# ST25R.net
KiCad netlist of a schematic drawn in Altium Designer
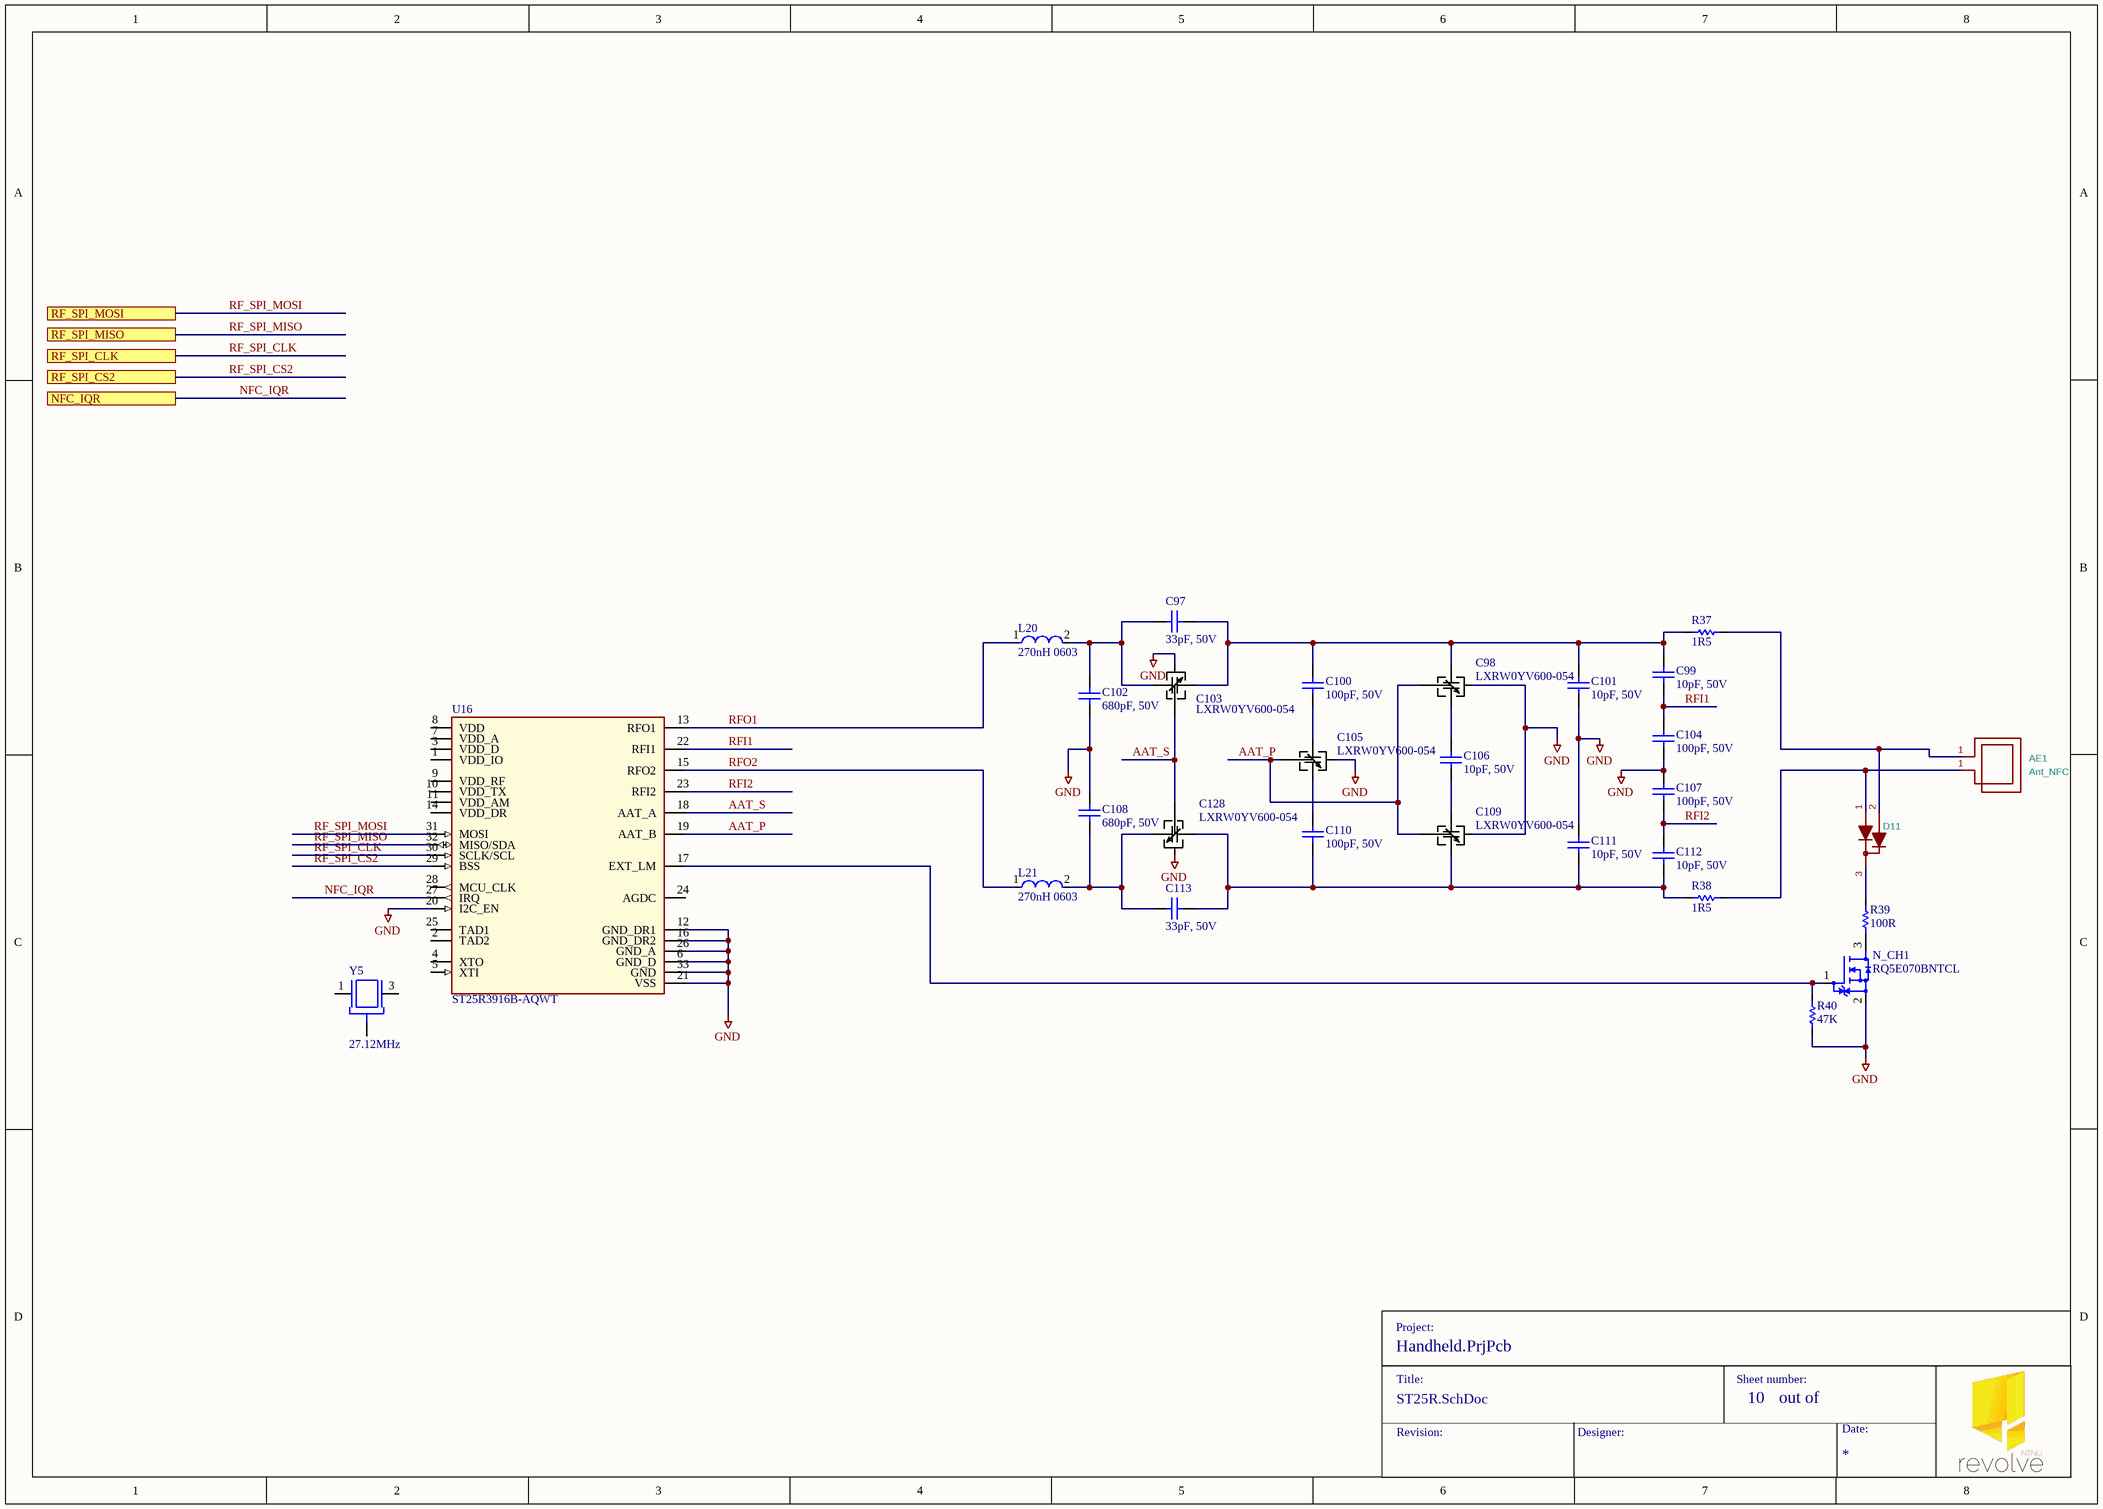
[diagram p0: ST25R.SchDoc]

(export (version "E")
  (design (tool "Eeschema 10.0.6"))
  (components
    (comp (ref "AE1")
      (value "Ant_NFC")
      (footprint "Jarvis_NFC_Ant")
      (libsource (lib "Lol_20230821") (part "Ant_NFC"))
    )
    (comp (ref "C97")
      (value "33pF, 50V")
      (footprint "0402 resistor")
      (description "50V 33pF C0G ±1% 0402 Multilayer Ceramic Capacitors MLCC - SMD/SMT ROHS")
      (fields (field (name "TOLERANCE") "1%"))
      (libsource (lib "Revolve NTNU") (part "CAP"))
    )
    (comp (ref "C98")
      (value "LXRW0YV600-054")
      (footprint "LXRW0_MUR-M")
      (description "Variable capacitor 30-60pF")
      (libsource (lib "Handheld") (part "LXRW0YV600"))
    )
    (comp (ref "C99")
      (value "10pF, 50V")
      (footprint "0402 resistor")
      (description "10pF, 50V, 10%, 0402")
      (libsource (lib "Revolve NTNU") (part "CAP"))
    )
    (comp (ref "C100")
      (value "100pF, 50V")
      (footprint "0402 resistor")
      (description "100pF, 50V, Tolerance, Temperature, 0402")
      (libsource (lib "Revolve NTNU") (part "CAP"))
    )
    (comp (ref "C101")
      (value "10pF, 50V")
      (footprint "0402 resistor")
      (description "10pF, 50V, 10%, 0402")
      (libsource (lib "Revolve NTNU") (part "CAP"))
    )
    (comp (ref "C102")
      (value "680pF, 50V")
      (footprint "0402 resistor")
      (fields (field (name "TOLERANCE") "1%"))
      (libsource (lib "Revolve NTNU") (part "CAP"))
    )
    (comp (ref "C103")
      (value "LXRW0YV600-054")
      (footprint "LXRW0_MUR-M")
      (description "Variable capacitor 30-60pF")
      (libsource (lib "Handheld") (part "LXRW0YV600"))
    )
    (comp (ref "C104")
      (value "100pF, 50V")
      (footprint "0402 resistor")
      (description "100pF, 50V, Tolerance, Temperature, 0402")
      (libsource (lib "Revolve NTNU") (part "CAP"))
    )
    (comp (ref "C105")
      (value "LXRW0YV600-054")
      (footprint "LXRW0_MUR-M")
      (description "Variable capacitor 30-60pF")
      (libsource (lib "Handheld") (part "LXRW0YV600"))
    )
    (comp (ref "C106")
      (value "10pF, 50V")
      (footprint "0402 resistor")
      (description "10pF, 50V, 10%, 0402")
      (libsource (lib "Revolve NTNU") (part "CAP"))
    )
    (comp (ref "C107")
      (value "100pF, 50V")
      (footprint "0402 resistor")
      (description "100pF, 50V, Tolerance, Temperature, 0402")
      (libsource (lib "Revolve NTNU") (part "CAP"))
    )
    (comp (ref "C108")
      (value "680pF, 50V")
      (footprint "0402 resistor")
      (fields (field (name "TOLERANCE") "1%"))
      (libsource (lib "Revolve NTNU") (part "CAP"))
    )
    (comp (ref "C109")
      (value "LXRW0YV600-054")
      (footprint "LXRW0_MUR-M")
      (description "Variable capacitor 30-60pF")
      (libsource (lib "Handheld") (part "LXRW0YV600"))
    )
    (comp (ref "C110")
      (value "100pF, 50V")
      (footprint "0402 resistor")
      (description "100pF, 50V, Tolerance, Temperature, 0402")
      (libsource (lib "Revolve NTNU") (part "CAP"))
    )
    (comp (ref "C111")
      (value "10pF, 50V")
      (footprint "0402 resistor")
      (description "10pF, 50V, 10%, 0402")
      (libsource (lib "Revolve NTNU") (part "CAP"))
    )
    (comp (ref "C112")
      (value "10pF, 50V")
      (footprint "0402 resistor")
      (description "10pF, 50V, 10%, 0402")
      (libsource (lib "Revolve NTNU") (part "CAP"))
    )
    (comp (ref "C113")
      (value "33pF, 50V")
      (footprint "0402 resistor")
      (description "50V 33pF C0G ±1% 0402 Multilayer Ceramic Capacitors MLCC - SMD/SMT ROHS")
      (fields (field (name "TOLERANCE") "1%"))
      (libsource (lib "Revolve NTNU") (part "CAP"))
    )
    (comp (ref "C128")
      (value "LXRW0YV600-054")
      (footprint "LXRW0_MUR-M")
      (description "Variable capacitor 30-60pF")
      (libsource (lib "Handheld") (part "LXRW0YV600"))
    )
    (comp (ref "D11")
      (value "BAV70W-7-F")
      (footprint "SOT65P210X100-3N")
      (libsource (lib "Lol_20230821") (part "BAV70W-7-F"))
    )
    (comp (ref "L20")
      (value "270nH 0603")
      (footprint "INDC1608X95N")
      (description "Multilayer Type Inductor for Power Lines, 0603, 270nH, 30%, 0.286Ω, 500mA, MLJ1608WR27JT000")
      (fields (field (name "TOLERANCE") "30%"))
      (libsource (lib "Handheld") (part "Inductor SMD 270nH"))
    )
    (comp (ref "L21")
      (value "270nH 0603")
      (footprint "INDC1608X95N")
      (description "Multilayer Type Inductor for Power Lines, 0603, 270nH, 30%, 0.286Ω, 500mA, MLJ1608WR27JT000")
      (fields (field (name "TOLERANCE") "30%"))
      (libsource (lib "Handheld") (part "Inductor SMD 270nH"))
    )
    (comp (ref "N_CH1")
      (value "RQ5E070BNTCL")
      (footprint "RTR040N03HZGTL-Footprint-1")
      (libsource (lib "Revolve NTNU") (part "RQ5E070BNTCL"))
    )
    (comp (ref "R37")
      (value "1R5")
      (footprint "RESC1005X40X25ML05T05")
      (description "1R5 1% 1/8W, 0402")
      (fields (field (name "TOLERANCE") "1%"))
      (libsource (lib "Revolve NTNU") (part "Resistor"))
    )
    (comp (ref "R38")
      (value "1R5")
      (footprint "RESC1005X40X25ML05T05")
      (description "1R5 1% 1/8W, 0402")
      (fields (field (name "TOLERANCE") "1%"))
      (libsource (lib "Revolve NTNU") (part "Resistor"))
    )
    (comp (ref "R39")
      (value "100R")
      (footprint "RESC1005X40X25ML05T05")
      (description "100R 1% 1/8W, 0402")
      (fields (field (name "TOLERANCE") "1%"))
      (libsource (lib "Revolve NTNU") (part "Resistor"))
    )
    (comp (ref "R40")
      (value "47K")
      (footprint "0603 Resistor")
      (description "47K, 1%, 1/10W, 0603")
      (libsource (lib "Revolve NTNU") (part "Resistor"))
    )
    (comp (ref "U16")
      (value "ST25R3916B-AQWT")
      (footprint "VFQFPN32_5X5_WETTABLE_STM-M")
      (description "NFC reader for payment, consumer and industrial")
      (fields (field (name "COPYRIGHT") "Copyright (C) 2025 Ultra Librarian. All rights reserved."))
      (libsource (lib "Handheld") (part "ST25R3916B-AQWT"))
    )
    (comp (ref "Y5")
      (value "27.12MHz")
      (footprint "XTAL_ECS-400-10-37B2-CKM-TR")
      (description "Crystal 27.12MHz ±10ppm (Tol) ±10ppm (Stability) 10pF FUND 60Ohm 4-Pin Mini-CSMD T/R")
      (fields (field (name "MF") "ECS Inc.") (field (name "MP") "ECS-400-10-37B2-CKM-TR"))
      (libsource (lib "Handheld") (part "ECS-271.2-10-37-CKM-TR"))
    )
  )
  (nets
    (net (code "1") (name "/AAT_P") (class "Default")
      (node (ref "C105") (pin "2") (pinfunction "VT_2") (pintype "passive"))
      (node (ref "C109") (pin "2") (pinfunction "VT_2") (pintype "passive"))
      (node (ref "C98") (pin "2") (pinfunction "VT_2") (pintype "passive"))
      (node (ref "U16") (pin "19") (pinfunction "AAT_B_19") (pintype "passive"))
    )
    (net (code "2") (name "/AAT_S") (class "Default")
      (node (ref "C103") (pin "2") (pinfunction "VT_2") (pintype "passive"))
      (node (ref "C128") (pin "2") (pinfunction "VT_2") (pintype "passive"))
      (node (ref "U16") (pin "18") (pinfunction "AAT_A_18") (pintype "passive"))
    )
    (net (code "3") (name "/NFC_IQR") (class "Default")
      (node (ref "U16") (pin "27") (pinfunction "IRQ_27") (pintype "output"))
    )
    (net (code "4") (name "/RFI1") (class "Default")
      (node (ref "C104") (pin "2") (pinfunction "2_2") (pintype "passive"))
      (node (ref "C99") (pin "1") (pinfunction "1_1") (pintype "passive"))
      (node (ref "U16") (pin "22") (pinfunction "RFI1_22") (pintype "passive"))
    )
    (net (code "5") (name "/RFI2") (class "Default")
      (node (ref "C107") (pin "1") (pinfunction "1_1") (pintype "passive"))
      (node (ref "C112") (pin "2") (pinfunction "2_2") (pintype "passive"))
      (node (ref "U16") (pin "23") (pinfunction "RFI2_23") (pintype "passive"))
    )
    (net (code "6") (name "/RFO1") (class "Default")
      (node (ref "L20") (pin "1") (pinfunction "1_1") (pintype "passive"))
      (node (ref "U16") (pin "13") (pinfunction "RFO1_13") (pintype "passive"))
    )
    (net (code "7") (name "/RFO2") (class "Default")
      (node (ref "L21") (pin "1") (pinfunction "1_1") (pintype "passive"))
      (node (ref "U16") (pin "15") (pinfunction "RFO2_15") (pintype "passive"))
    )
    (net (code "8") (name "/RF_SPI_CLK") (class "Default")
      (node (ref "U16") (pin "30") (pinfunction "SCLK/SCL_30") (pintype "input"))
    )
    (net (code "9") (name "/RF_SPI_CS2") (class "Default")
      (node (ref "U16") (pin "29") (pinfunction "BSS_29") (pintype "input"))
    )
    (net (code "10") (name "/RF_SPI_MISO") (class "Default")
      (node (ref "U16") (pin "32") (pinfunction "MISO/SDA_32") (pintype "bidirectional"))
    )
    (net (code "11") (name "/RF_SPI_MOSI") (class "Default")
      (node (ref "U16") (pin "31") (pinfunction "MOSI_31") (pintype "input"))
    )
    (net (code "12") (name "GND") (class "Default")
      (node (ref "C101") (pin "1") (pinfunction "1_1") (pintype "passive"))
      (node (ref "C102") (pin "1") (pinfunction "1_1") (pintype "passive"))
      (node (ref "C103") (pin "1") (pinfunction "GND_1") (pintype "power_in"))
      (node (ref "C104") (pin "1") (pinfunction "1_1") (pintype "passive"))
      (node (ref "C105") (pin "1") (pinfunction "GND_1") (pintype "power_in"))
      (node (ref "C107") (pin "2") (pinfunction "2_2") (pintype "passive"))
      (node (ref "C108") (pin "2") (pinfunction "2_2") (pintype "passive"))
      (node (ref "C109") (pin "1") (pinfunction "GND_1") (pintype "power_in"))
      (node (ref "C111") (pin "2") (pinfunction "2_2") (pintype "passive"))
      (node (ref "C128") (pin "1") (pinfunction "GND_1") (pintype "power_in"))
      (node (ref "C98") (pin "1") (pinfunction "GND_1") (pintype "power_in"))
      (node (ref "N_CH1") (pin "2") (pinfunction "S_2") (pintype "passive"))
      (node (ref "R40") (pin "1") (pinfunction "1_1") (pintype "passive"))
      (node (ref "U16") (pin "12") (pinfunction "GND_DR1_12") (pintype "power_in"))
      (node (ref "U16") (pin "16") (pinfunction "GND_DR2_16") (pintype "power_in"))
      (node (ref "U16") (pin "20") (pinfunction "I2C_EN_20") (pintype "input"))
      (node (ref "U16") (pin "21") (pinfunction "VSS_21") (pintype "power_in"))
      (node (ref "U16") (pin "26") (pinfunction "GND_A_26") (pintype "power_in"))
      (node (ref "U16") (pin "33") (pinfunction "GND_33") (pintype "power_in"))
      (node (ref "U16") (pin "6") (pinfunction "GND_D_6") (pintype "power_in"))
    )
    (net (code "13") (name "Net-(AE1-Pad1)") (class "Default")
      (node (ref "AE1") (pin "1") (pinfunction "1_1") (pintype "passive"))
      (node (ref "D11") (pin "2") (pinfunction "2_2") (pintype "passive"))
      (node (ref "R37") (pin "2") (pinfunction "2_2") (pintype "passive"))
    )
    (net (code "14") (name "Net-(AE1-Pad1)_1") (class "Default")
      (node (ref "AE1") (pin "1") (pinfunction "1_1") (pintype "passive"))
      (node (ref "D11") (pin "1") (pinfunction "1_1") (pintype "passive"))
      (node (ref "R38") (pin "2") (pinfunction "2_2") (pintype "passive"))
    )
    (net (code "15") (name "Net-(C98-PORT2)") (class "Default")
      (node (ref "C106") (pin "2") (pinfunction "2_2") (pintype "passive"))
      (node (ref "C98") (pin "4") (pinfunction "PORT2_4") (pintype "bidirectional"))
    )
    (net (code "16") (name "Net-(C103-PORT1)") (class "Default")
      (node (ref "C102") (pin "2") (pinfunction "2_2") (pintype "passive"))
      (node (ref "C103") (pin "3") (pinfunction "PORT1_3") (pintype "bidirectional"))
      (node (ref "C97") (pin "1") (pinfunction "1_1") (pintype "passive"))
      (node (ref "L20") (pin "2") (pinfunction "2_2") (pintype "passive"))
    )
    (net (code "17") (name "Net-(C103-PORT2)") (class "Default")
      (node (ref "C100") (pin "2") (pinfunction "2_2") (pintype "passive"))
      (node (ref "C101") (pin "2") (pinfunction "2_2") (pintype "passive"))
      (node (ref "C103") (pin "4") (pinfunction "PORT2_4") (pintype "bidirectional"))
      (node (ref "C97") (pin "2") (pinfunction "2_2") (pintype "passive"))
      (node (ref "C98") (pin "3") (pinfunction "PORT1_3") (pintype "bidirectional"))
      (node (ref "C99") (pin "2") (pinfunction "2_2") (pintype "passive"))
      (node (ref "R37") (pin "1") (pinfunction "1_1") (pintype "passive"))
    )
    (net (code "18") (name "Net-(C105-PORT1)") (class "Default")
      (node (ref "C100") (pin "1") (pinfunction "1_1") (pintype "passive"))
      (node (ref "C105") (pin "3") (pinfunction "PORT1_3") (pintype "bidirectional"))
    )
    (net (code "19") (name "Net-(C105-PORT2)") (class "Default")
      (node (ref "C105") (pin "4") (pinfunction "PORT2_4") (pintype "bidirectional"))
      (node (ref "C110") (pin "2") (pinfunction "2_2") (pintype "passive"))
    )
    (net (code "20") (name "Net-(C109-PORT1)") (class "Default")
      (node (ref "C106") (pin "1") (pinfunction "1_1") (pintype "passive"))
      (node (ref "C109") (pin "3") (pinfunction "PORT1_3") (pintype "bidirectional"))
    )
    (net (code "21") (name "Net-(C109-PORT2)") (class "Default")
      (node (ref "C109") (pin "4") (pinfunction "PORT2_4") (pintype "bidirectional"))
      (node (ref "C110") (pin "1") (pinfunction "1_1") (pintype "passive"))
      (node (ref "C111") (pin "1") (pinfunction "1_1") (pintype "passive"))
      (node (ref "C112") (pin "1") (pinfunction "1_1") (pintype "passive"))
      (node (ref "C113") (pin "2") (pinfunction "2_2") (pintype "passive"))
      (node (ref "C128") (pin "3") (pinfunction "PORT1_3") (pintype "bidirectional"))
      (node (ref "R38") (pin "1") (pinfunction "1_1") (pintype "passive"))
    )
    (net (code "22") (name "Net-(C128-PORT2)") (class "Default")
      (node (ref "C108") (pin "1") (pinfunction "1_1") (pintype "passive"))
      (node (ref "C113") (pin "1") (pinfunction "1_1") (pintype "passive"))
      (node (ref "C128") (pin "4") (pinfunction "PORT2_4") (pintype "bidirectional"))
      (node (ref "L21") (pin "2") (pinfunction "2_2") (pintype "passive"))
    )
    (net (code "23") (name "Net-(D11-Pad3)") (class "Default")
      (node (ref "D11") (pin "3") (pinfunction "3_3") (pintype "passive"))
      (node (ref "R39") (pin "2") (pinfunction "2_2") (pintype "passive"))
    )
    (net (code "24") (name "Net-(N_CH1-D)") (class "Default")
      (node (ref "N_CH1") (pin "3") (pinfunction "D_3") (pintype "passive"))
      (node (ref "R39") (pin "1") (pinfunction "1_1") (pintype "passive"))
    )
    (net (code "25") (name "Net-(N_CH1-G)") (class "Default")
      (node (ref "N_CH1") (pin "1") (pinfunction "G_1") (pintype "passive"))
      (node (ref "R40") (pin "2") (pinfunction "2_2") (pintype "passive"))
      (node (ref "U16") (pin "17") (pinfunction "EXT_LM_17") (pintype "passive"))
    )
    (net (code "26") (name "Net-(Y5-GND-Pad2)") (class "Default")
      (node (ref "Y5") (pin "2") (pinfunction "GND_2") (pintype "power_in"))
      (node (ref "Y5") (pin "4") (pinfunction "GND_4") (pintype "power_in"))
    )
    (net (code "27") (name "unconnected-(U16-AGDC-Pad24)") (class "Default")
      (node (ref "U16") (pin "24") (pinfunction "AGDC_24") (pintype "passive"))
    )
    (net (code "28") (name "unconnected-(U16-MCU_CLK-Pad28)") (class "Default")
      (node (ref "U16") (pin "28") (pinfunction "MCU_CLK_28") (pintype "output"))
    )
    (net (code "29") (name "unconnected-(U16-TAD1-Pad25)") (class "Default")
      (node (ref "U16") (pin "25") (pinfunction "TAD1_25") (pintype "passive"))
    )
    (net (code "30") (name "unconnected-(U16-TAD2-Pad2)") (class "Default")
      (node (ref "U16") (pin "2") (pinfunction "TAD2_2") (pintype "passive"))
    )
    (net (code "31") (name "unconnected-(U16-VDD-Pad8)") (class "Default")
      (node (ref "U16") (pin "8") (pinfunction "VDD_8") (pintype "power_in"))
    )
    (net (code "32") (name "unconnected-(U16-VDD_A-Pad7)") (class "Default")
      (node (ref "U16") (pin "7") (pinfunction "VDD_A_7") (pintype "passive"))
    )
    (net (code "33") (name "unconnected-(U16-VDD_AM-Pad11)") (class "Default")
      (node (ref "U16") (pin "11") (pinfunction "VDD_AM_11") (pintype "passive"))
    )
    (net (code "34") (name "unconnected-(U16-VDD_D-Pad3)") (class "Default")
      (node (ref "U16") (pin "3") (pinfunction "VDD_D_3") (pintype "passive"))
    )
    (net (code "35") (name "unconnected-(U16-VDD_DR-Pad14)") (class "Default")
      (node (ref "U16") (pin "14") (pinfunction "VDD_DR_14") (pintype "power_in"))
    )
    (net (code "36") (name "unconnected-(U16-VDD_IO-Pad1)") (class "Default")
      (node (ref "U16") (pin "1") (pinfunction "VDD_IO_1") (pintype "power_in"))
    )
    (net (code "37") (name "unconnected-(U16-VDD_RF-Pad9)") (class "Default")
      (node (ref "U16") (pin "9") (pinfunction "VDD_RF_9") (pintype "passive"))
    )
    (net (code "38") (name "unconnected-(U16-VDD_TX-Pad10)") (class "Default")
      (node (ref "U16") (pin "10") (pinfunction "VDD_TX_10") (pintype "power_in"))
    )
    (net (code "39") (name "unconnected-(U16-XTI-Pad5)") (class "Default")
      (node (ref "U16") (pin "5") (pinfunction "XTI_5") (pintype "input"))
    )
    (net (code "40") (name "unconnected-(U16-XTO-Pad4)") (class "Default")
      (node (ref "U16") (pin "4") (pinfunction "XTO_4") (pintype "passive"))
    )
    (net (code "41") (name "unconnected-(Y5-IN{slash}OUT-Pad1)") (class "Default")
      (node (ref "Y5") (pin "1") (pinfunction "IN/OUT_1") (pintype "passive"))
    )
    (net (code "42") (name "unconnected-(Y5-OUT{slash}IN-Pad3)") (class "Default")
      (node (ref "Y5") (pin "3") (pinfunction "OUT/IN_3") (pintype "passive"))
    )
  )
)
